# MCU.net
KiCad netlist of a schematic drawn in Altium Designer
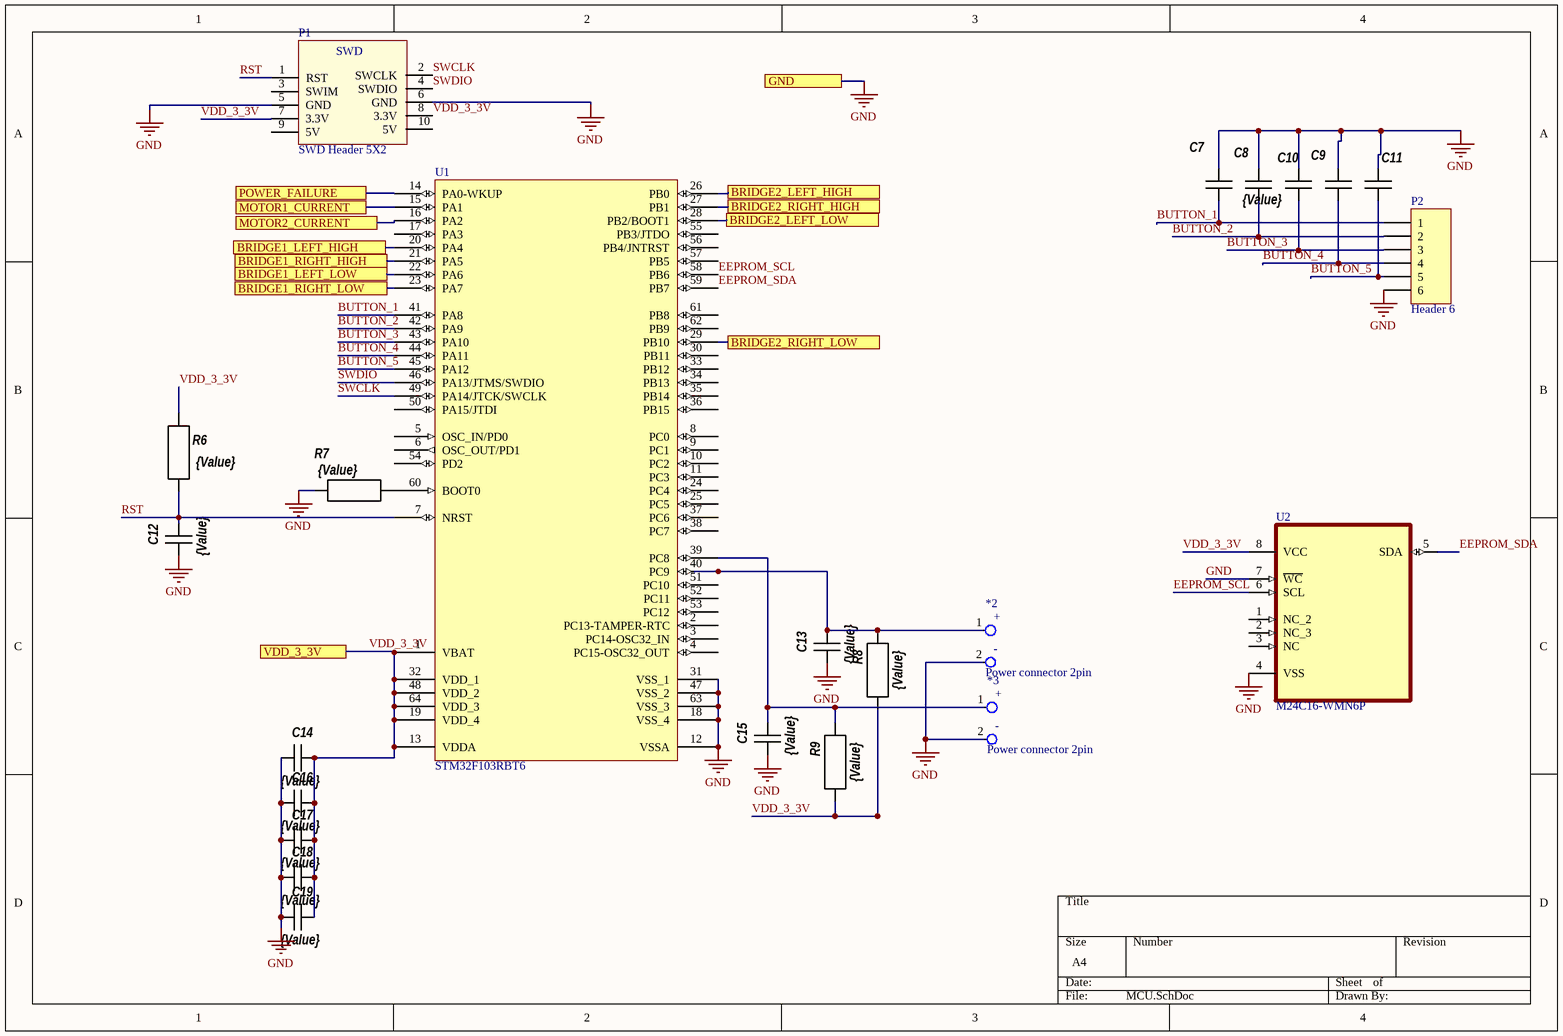
[diagram p0: MCU.SchDoc]

(export (version "E")
  (design (tool "Eeschema 10.0.6"))
  (components
    (comp (ref "*2")
      (value "Power connector 2pin")
      (footprint "Power connector 2 pin")
      (libsource (lib "Integrated_Library1") (part "Power connector 2pin"))
    )
    (comp (ref "*3")
      (value "Power connector 2pin")
      (footprint "Power connector 2 pin")
      (libsource (lib "Integrated_Library1") (part "Power connector 2pin"))
    )
    (comp (ref "C7")
      (value "{Value}")
      (footprint "R0805")
      (description "Конденсатор 0805")
      (fields (field (name "MANUFACTURER") "Murata") (field (name "Comment") "Cap 0805"))
      (libsource (lib "УГО") (part "Cap 0805"))
    )
    (comp (ref "C8")
      (value "Cap 0805")
      (footprint "R0805")
      (description "Конденсатор 0805")
      (fields (field (name "MANUFACTURER") "Murata"))
      (libsource (lib "УГО") (part "Cap 0805"))
    )
    (comp (ref "C9")
      (value "Cap 0805")
      (footprint "R0805")
      (description "Конденсатор 0805")
      (fields (field (name "MANUFACTURER") "Murata"))
      (libsource (lib "УГО") (part "Cap 0805"))
    )
    (comp (ref "C10")
      (value "Cap 0805")
      (footprint "R0805")
      (description "Конденсатор 0805")
      (fields (field (name "MANUFACTURER") "Murata"))
      (libsource (lib "УГО") (part "Cap 0805"))
    )
    (comp (ref "C11")
      (value "Cap 0805")
      (footprint "R0805")
      (description "Конденсатор 0805")
      (fields (field (name "MANUFACTURER") "Murata"))
      (libsource (lib "УГО") (part "Cap 0805"))
    )
    (comp (ref "C12")
      (value "{Value}")
      (footprint "R0805")
      (description "Конденсатор 0805")
      (fields (field (name "MANUFACTURER") "Murata") (field (name "Comment") "Cap 0805"))
      (libsource (lib "УГО") (part "Cap 0805"))
    )
    (comp (ref "C13")
      (value "{Value}")
      (footprint "R0805")
      (description "Конденсатор 0805")
      (fields (field (name "MANUFACTURER") "Murata") (field (name "Comment") "Cap 0805"))
      (libsource (lib "УГО") (part "Cap 0805"))
    )
    (comp (ref "C14")
      (value "{Value}")
      (footprint "R0805")
      (description "Конденсатор 0805")
      (fields (field (name "MANUFACTURER") "Murata") (field (name "Comment") "Cap 0805"))
      (libsource (lib "УГО") (part "Cap 0805"))
    )
    (comp (ref "C15")
      (value "{Value}")
      (footprint "R0805")
      (description "Конденсатор 0805")
      (fields (field (name "MANUFACTURER") "Murata") (field (name "Comment") "Cap 0805"))
      (libsource (lib "УГО") (part "Cap 0805"))
    )
    (comp (ref "C16")
      (value "{Value}")
      (footprint "R0805")
      (description "Конденсатор 0805")
      (fields (field (name "MANUFACTURER") "Murata") (field (name "Comment") "Cap 0805"))
      (libsource (lib "УГО") (part "Cap 0805"))
    )
    (comp (ref "C17")
      (value "{Value}")
      (footprint "R0805")
      (description "Конденсатор 0805")
      (fields (field (name "MANUFACTURER") "Murata") (field (name "Comment") "Cap 0805"))
      (libsource (lib "УГО") (part "Cap 0805"))
    )
    (comp (ref "C18")
      (value "{Value}")
      (footprint "R0805")
      (description "Конденсатор 0805")
      (fields (field (name "MANUFACTURER") "Murata") (field (name "Comment") "Cap 0805"))
      (libsource (lib "УГО") (part "Cap 0805"))
    )
    (comp (ref "C19")
      (value "{Value}")
      (footprint "R0805")
      (description "Конденсатор 0805")
      (fields (field (name "MANUFACTURER") "Murata") (field (name "Comment") "Cap 0805"))
      (libsource (lib "УГО") (part "Cap 0805"))
    )
    (comp (ref "P1")
      (value "SWD Header 5X2")
      (footprint "HDR2X5")
      (description "Header, 5-Pin, Dual row")
      (fields (field (name "PUBLISHER") "Altium Limited"))
      (libsource (lib "Integrated_Library1") (part "SWD Header 5X2"))
    )
    (comp (ref "P2")
      (value "Header 6")
      (footprint "HDR1X6")
      (description "Header, 6-Pin")
      (fields (field (name "PUBLISHER") "Altium Limited"))
      (libsource (lib "Miscellaneous Connectors") (part "Header 6"))
    )
    (comp (ref "R6")
      (value "{Value}")
      (footprint "R0805")
      (description "Резистор 0805")
      (fields (field (name "MANUFACTURER") "Yageo") (field (name "Comment") "Res 0805"))
      (libsource (lib "GIS_SMD components") (part "Res 0805"))
    )
    (comp (ref "R7")
      (value "{Value}")
      (footprint "R0805")
      (description "Резистор 0805")
      (fields (field (name "MANUFACTURER") "Yageo") (field (name "Comment") "Res 0805"))
      (libsource (lib "GIS_SMD components") (part "Res 0805"))
    )
    (comp (ref "R8")
      (value "{Value}")
      (footprint "R0805")
      (description "Резистор 0805")
      (fields (field (name "MANUFACTURER") "Yageo") (field (name "Comment") "Res 0805"))
      (libsource (lib "GIS_SMD components") (part "Res 0805"))
    )
    (comp (ref "R9")
      (value "{Value}")
      (footprint "R0805")
      (description "Резистор 0805")
      (fields (field (name "MANUFACTURER") "Yageo") (field (name "Comment") "Res 0805"))
      (libsource (lib "GIS_SMD components") (part "Res 0805"))
    )
    (comp (ref "U1")
      (value "STM32F103RBT6")
      (footprint "LQFP64_N")
      (description "STM32 ARM-based 32-bit MCU with 128 Kbytes Flash, 64-pin LQFP, Industrial Temperature")
      (fields (field (name "PUBLISHER") "Altium Limited"))
      (libsource (lib "ST Microcontroller 32-Bit STM32") (part "STM32F103RBT6"))
    )
    (comp (ref "U2")
      (value "M24C16-WMN6P")
      (footprint "SOIC127P600X175-8N")
      (description "EEPROM Memory IC 16Kb _2K x 8_ IÂ²C 400kHz 900ns 8-SO")
      (fields (field (name "MF") "STMicroelectronics"))
      (libsource (lib "M24C16-WMN6P") (part "M24C16-WMN6P"))
    )
  )
  (nets
    (net (code "1") (name "/BRIDGE1_LEFT_HIGH") (class "Default")
      (node (ref "U1") (pin "20") (pinfunction "PA4_20") (pintype "bidirectional"))
    )
    (net (code "2") (name "/BRIDGE1_LEFT_LOW") (class "Default")
      (node (ref "U1") (pin "22") (pinfunction "PA6_22") (pintype "bidirectional"))
    )
    (net (code "3") (name "/BRIDGE1_RIGHT_HIGH") (class "Default")
      (node (ref "U1") (pin "21") (pinfunction "PA5_21") (pintype "bidirectional"))
    )
    (net (code "4") (name "/BRIDGE1_RIGHT_LOW") (class "Default")
      (node (ref "U1") (pin "23") (pinfunction "PA7_23") (pintype "bidirectional"))
    )
    (net (code "5") (name "/BRIDGE2_LEFT_HIGH") (class "Default")
      (node (ref "U1") (pin "26") (pinfunction "PB0_26") (pintype "bidirectional"))
    )
    (net (code "6") (name "/BRIDGE2_LEFT_LOW") (class "Default")
      (node (ref "U1") (pin "28") (pinfunction "PB2/BOOT1_28") (pintype "bidirectional"))
    )
    (net (code "7") (name "/BRIDGE2_RIGHT_HIGH") (class "Default")
      (node (ref "U1") (pin "27") (pinfunction "PB1_27") (pintype "bidirectional"))
    )
    (net (code "8") (name "/BRIDGE2_RIGHT_LOW") (class "Default")
      (node (ref "U1") (pin "29") (pinfunction "PB10_29") (pintype "bidirectional"))
    )
    (net (code "9") (name "/BUTTON_1") (class "Default")
      (node (ref "C7") (pin "1") (pinfunction "1_1") (pintype "passive"))
      (node (ref "P2") (pin "1") (pinfunction "1_1") (pintype "passive"))
      (node (ref "U1") (pin "41") (pinfunction "PA8_41") (pintype "bidirectional"))
    )
    (net (code "10") (name "/BUTTON_2") (class "Default")
      (node (ref "C8") (pin "1") (pinfunction "1_1") (pintype "passive"))
      (node (ref "P2") (pin "2") (pinfunction "2_2") (pintype "passive"))
      (node (ref "U1") (pin "42") (pinfunction "PA9_42") (pintype "bidirectional"))
    )
    (net (code "11") (name "/BUTTON_3") (class "Default")
      (node (ref "C10") (pin "1") (pinfunction "1_1") (pintype "passive"))
      (node (ref "P2") (pin "3") (pinfunction "3_3") (pintype "passive"))
      (node (ref "U1") (pin "43") (pinfunction "PA10_43") (pintype "bidirectional"))
    )
    (net (code "12") (name "/BUTTON_4") (class "Default")
      (node (ref "C9") (pin "1") (pinfunction "1_1") (pintype "passive"))
      (node (ref "P2") (pin "4") (pinfunction "4_4") (pintype "passive"))
      (node (ref "U1") (pin "44") (pinfunction "PA11_44") (pintype "bidirectional"))
    )
    (net (code "13") (name "/BUTTON_5") (class "Default")
      (node (ref "C11") (pin "1") (pinfunction "1_1") (pintype "passive"))
      (node (ref "P2") (pin "5") (pinfunction "5_5") (pintype "passive"))
      (node (ref "U1") (pin "45") (pinfunction "PA12_45") (pintype "bidirectional"))
    )
    (net (code "14") (name "/EEPROM_SCL") (class "Default")
      (node (ref "U1") (pin "58") (pinfunction "PB6_58") (pintype "bidirectional"))
      (node (ref "U2") (pin "6") (pinfunction "SCL_6") (pintype "input"))
    )
    (net (code "15") (name "/EEPROM_SDA") (class "Default")
      (node (ref "U1") (pin "59") (pinfunction "PB7_59") (pintype "bidirectional"))
      (node (ref "U2") (pin "5") (pinfunction "SDA_5") (pintype "bidirectional"))
    )
    (net (code "16") (name "/MOTOR1_CURRENT") (class "Default")
      (node (ref "U1") (pin "15") (pinfunction "PA1_15") (pintype "bidirectional"))
    )
    (net (code "17") (name "/MOTOR2_CURRENT") (class "Default")
      (node (ref "U1") (pin "16") (pinfunction "PA2_16") (pintype "bidirectional"))
    )
    (net (code "18") (name "/POWER_FAILURE") (class "Default")
      (node (ref "U1") (pin "14") (pinfunction "PA0-WKUP_14") (pintype "bidirectional"))
    )
    (net (code "19") (name "/RST") (class "Default")
      (node (ref "C12") (pin "2") (pinfunction "2_2") (pintype "passive"))
      (node (ref "P1") (pin "1") (pinfunction "RST_1") (pintype "passive"))
      (node (ref "R6") (pin "1") (pinfunction "1_1") (pintype "passive"))
      (node (ref "U1") (pin "7") (pinfunction "NRST_7") (pintype "bidirectional"))
    )
    (net (code "20") (name "/SWCLK") (class "Default")
      (node (ref "P1") (pin "2") (pinfunction "SWCLK_2") (pintype "passive"))
      (node (ref "U1") (pin "49") (pinfunction "PA14/JTCK/SWCLK_49") (pintype "bidirectional"))
    )
    (net (code "21") (name "/SWDIO") (class "Default")
      (node (ref "P1") (pin "4") (pinfunction "SWDIO_4") (pintype "passive"))
      (node (ref "U1") (pin "46") (pinfunction "PA13/JTMS/SWDIO_46") (pintype "bidirectional"))
    )
    (net (code "22") (name "/VDD_3_3V") (class "Default")
      (node (ref "C14") (pin "2") (pinfunction "2_2") (pintype "passive"))
      (node (ref "C16") (pin "2") (pinfunction "2_2") (pintype "passive"))
      (node (ref "C17") (pin "2") (pinfunction "2_2") (pintype "passive"))
      (node (ref "C18") (pin "2") (pinfunction "2_2") (pintype "passive"))
      (node (ref "C19") (pin "2") (pinfunction "2_2") (pintype "passive"))
      (node (ref "P1") (pin "7") (pinfunction "3.3V_7") (pintype "passive"))
      (node (ref "P1") (pin "8") (pinfunction "3.3V_8") (pintype "passive"))
      (node (ref "R6") (pin "2") (pinfunction "2_2") (pintype "passive"))
      (node (ref "R8") (pin "1") (pinfunction "1_1") (pintype "passive"))
      (node (ref "R9") (pin "1") (pinfunction "1_1") (pintype "passive"))
      (node (ref "U1") (pin "1") (pinfunction "VBAT_1") (pintype "power_in"))
      (node (ref "U1") (pin "13") (pinfunction "VDDA_13") (pintype "power_in"))
      (node (ref "U1") (pin "19") (pinfunction "VDD_4_19") (pintype "power_in"))
      (node (ref "U1") (pin "32") (pinfunction "VDD_1_32") (pintype "power_in"))
      (node (ref "U1") (pin "48") (pinfunction "VDD_2_48") (pintype "power_in"))
      (node (ref "U1") (pin "64") (pinfunction "VDD_3_64") (pintype "power_in"))
      (node (ref "U2") (pin "8") (pinfunction "VCC_8") (pintype "power_in"))
    )
    (net (code "23") (name "GND") (class "Default")
      (node (ref "*2") (pin "2") (pintype "passive"))
      (node (ref "*3") (pin "2") (pintype "passive"))
      (node (ref "C10") (pin "2") (pinfunction "2_2") (pintype "passive"))
      (node (ref "C11") (pin "2") (pinfunction "2_2") (pintype "passive"))
      (node (ref "C12") (pin "1") (pinfunction "1_1") (pintype "passive"))
      (node (ref "C13") (pin "1") (pinfunction "1_1") (pintype "passive"))
      (node (ref "C14") (pin "1") (pinfunction "1_1") (pintype "passive"))
      (node (ref "C15") (pin "1") (pinfunction "1_1") (pintype "passive"))
      (node (ref "C16") (pin "1") (pinfunction "1_1") (pintype "passive"))
      (node (ref "C17") (pin "1") (pinfunction "1_1") (pintype "passive"))
      (node (ref "C18") (pin "1") (pinfunction "1_1") (pintype "passive"))
      (node (ref "C19") (pin "1") (pinfunction "1_1") (pintype "passive"))
      (node (ref "C7") (pin "2") (pinfunction "2_2") (pintype "passive"))
      (node (ref "C8") (pin "2") (pinfunction "2_2") (pintype "passive"))
      (node (ref "C9") (pin "2") (pinfunction "2_2") (pintype "passive"))
      (node (ref "P1") (pin "5") (pinfunction "GND_5") (pintype "passive"))
      (node (ref "P1") (pin "6") (pinfunction "GND_6") (pintype "passive"))
      (node (ref "P2") (pin "6") (pinfunction "6_6") (pintype "passive"))
      (node (ref "R7") (pin "1") (pinfunction "1_1") (pintype "passive"))
      (node (ref "U1") (pin "12") (pinfunction "VSSA_12") (pintype "power_in"))
      (node (ref "U1") (pin "18") (pinfunction "VSS_4_18") (pintype "power_in"))
      (node (ref "U1") (pin "31") (pinfunction "VSS_1_31") (pintype "power_in"))
      (node (ref "U1") (pin "47") (pinfunction "VSS_2_47") (pintype "power_in"))
      (node (ref "U1") (pin "63") (pinfunction "VSS_3_63") (pintype "power_in"))
      (node (ref "U2") (pin "4") (pinfunction "VSS_4") (pintype "passive"))
      (node (ref "U2") (pin "7") (pinfunction "~{WC}_7") (pintype "input"))
    )
    (net (code "24") (name "Net-(U1-BOOT0)") (class "Default")
      (node (ref "R7") (pin "2") (pinfunction "2_2") (pintype "passive"))
      (node (ref "U1") (pin "60") (pinfunction "BOOT0_60") (pintype "input"))
    )
    (net (code "25") (name "Net-(U1-PC8)") (class "Default")
      (node (ref "*3") (pin "1") (pintype "passive"))
      (node (ref "C15") (pin "2") (pinfunction "2_2") (pintype "passive"))
      (node (ref "R9") (pin "2") (pinfunction "2_2") (pintype "passive"))
      (node (ref "U1") (pin "39") (pinfunction "PC8_39") (pintype "bidirectional"))
    )
    (net (code "26") (name "Net-(U1-PC9)") (class "Default")
      (node (ref "*2") (pin "1") (pintype "passive"))
      (node (ref "C13") (pin "2") (pinfunction "2_2") (pintype "passive"))
      (node (ref "R8") (pin "2") (pinfunction "2_2") (pintype "passive"))
      (node (ref "U1") (pin "40") (pinfunction "PC9_40") (pintype "bidirectional"))
    )
    (net (code "27") (name "unconnected-(P1-5V-Pad9)") (class "Default")
      (node (ref "P1") (pin "9") (pinfunction "5V_9") (pintype "passive"))
    )
    (net (code "28") (name "unconnected-(P1-5V-Pad10)") (class "Default")
      (node (ref "P1") (pin "10") (pinfunction "5V_10") (pintype "passive"))
    )
    (net (code "29") (name "unconnected-(P1-SWIM-Pad3)") (class "Default")
      (node (ref "P1") (pin "3") (pinfunction "SWIM_3") (pintype "passive"))
    )
    (net (code "30") (name "unconnected-(U1-OSC_IN{slash}PD0-Pad5)") (class "Default")
      (node (ref "U1") (pin "5") (pinfunction "OSC_IN/PD0_5") (pintype "input"))
    )
    (net (code "31") (name "unconnected-(U1-OSC_OUT{slash}PD1-Pad6)") (class "Default")
      (node (ref "U1") (pin "6") (pinfunction "OSC_OUT/PD1_6") (pintype "output"))
    )
    (net (code "32") (name "unconnected-(U1-PA3-Pad17)") (class "Default")
      (node (ref "U1") (pin "17") (pinfunction "PA3_17") (pintype "bidirectional"))
    )
    (net (code "33") (name "unconnected-(U1-PA15{slash}JTDI-Pad50)") (class "Default")
      (node (ref "U1") (pin "50") (pinfunction "PA15/JTDI_50") (pintype "bidirectional"))
    )
    (net (code "34") (name "unconnected-(U1-PB3{slash}JTDO-Pad55)") (class "Default")
      (node (ref "U1") (pin "55") (pinfunction "PB3/JTDO_55") (pintype "bidirectional"))
    )
    (net (code "35") (name "unconnected-(U1-PB4{slash}JNTRST-Pad56)") (class "Default")
      (node (ref "U1") (pin "56") (pinfunction "PB4/JNTRST_56") (pintype "bidirectional"))
    )
    (net (code "36") (name "unconnected-(U1-PB5-Pad57)") (class "Default")
      (node (ref "U1") (pin "57") (pinfunction "PB5_57") (pintype "bidirectional"))
    )
    (net (code "37") (name "unconnected-(U1-PB8-Pad61)") (class "Default")
      (node (ref "U1") (pin "61") (pinfunction "PB8_61") (pintype "bidirectional"))
    )
    (net (code "38") (name "unconnected-(U1-PB9-Pad62)") (class "Default")
      (node (ref "U1") (pin "62") (pinfunction "PB9_62") (pintype "bidirectional"))
    )
    (net (code "39") (name "unconnected-(U1-PB11-Pad30)") (class "Default")
      (node (ref "U1") (pin "30") (pinfunction "PB11_30") (pintype "bidirectional"))
    )
    (net (code "40") (name "unconnected-(U1-PB12-Pad33)") (class "Default")
      (node (ref "U1") (pin "33") (pinfunction "PB12_33") (pintype "bidirectional"))
    )
    (net (code "41") (name "unconnected-(U1-PB13-Pad34)") (class "Default")
      (node (ref "U1") (pin "34") (pinfunction "PB13_34") (pintype "bidirectional"))
    )
    (net (code "42") (name "unconnected-(U1-PB14-Pad35)") (class "Default")
      (node (ref "U1") (pin "35") (pinfunction "PB14_35") (pintype "bidirectional"))
    )
    (net (code "43") (name "unconnected-(U1-PB15-Pad36)") (class "Default")
      (node (ref "U1") (pin "36") (pinfunction "PB15_36") (pintype "bidirectional"))
    )
    (net (code "44") (name "unconnected-(U1-PC0-Pad8)") (class "Default")
      (node (ref "U1") (pin "8") (pinfunction "PC0_8") (pintype "bidirectional"))
    )
    (net (code "45") (name "unconnected-(U1-PC1-Pad9)") (class "Default")
      (node (ref "U1") (pin "9") (pinfunction "PC1_9") (pintype "bidirectional"))
    )
    (net (code "46") (name "unconnected-(U1-PC2-Pad10)") (class "Default")
      (node (ref "U1") (pin "10") (pinfunction "PC2_10") (pintype "bidirectional"))
    )
    (net (code "47") (name "unconnected-(U1-PC3-Pad11)") (class "Default")
      (node (ref "U1") (pin "11") (pinfunction "PC3_11") (pintype "bidirectional"))
    )
    (net (code "48") (name "unconnected-(U1-PC4-Pad24)") (class "Default")
      (node (ref "U1") (pin "24") (pinfunction "PC4_24") (pintype "bidirectional"))
    )
    (net (code "49") (name "unconnected-(U1-PC5-Pad25)") (class "Default")
      (node (ref "U1") (pin "25") (pinfunction "PC5_25") (pintype "bidirectional"))
    )
    (net (code "50") (name "unconnected-(U1-PC6-Pad37)") (class "Default")
      (node (ref "U1") (pin "37") (pinfunction "PC6_37") (pintype "bidirectional"))
    )
    (net (code "51") (name "unconnected-(U1-PC7-Pad38)") (class "Default")
      (node (ref "U1") (pin "38") (pinfunction "PC7_38") (pintype "bidirectional"))
    )
    (net (code "52") (name "unconnected-(U1-PC10-Pad51)") (class "Default")
      (node (ref "U1") (pin "51") (pinfunction "PC10_51") (pintype "bidirectional"))
    )
    (net (code "53") (name "unconnected-(U1-PC11-Pad52)") (class "Default")
      (node (ref "U1") (pin "52") (pinfunction "PC11_52") (pintype "bidirectional"))
    )
    (net (code "54") (name "unconnected-(U1-PC12-Pad53)") (class "Default")
      (node (ref "U1") (pin "53") (pinfunction "PC12_53") (pintype "bidirectional"))
    )
    (net (code "55") (name "unconnected-(U1-PC13-TAMPER-RTC-Pad2)") (class "Default")
      (node (ref "U1") (pin "2") (pinfunction "PC13-TAMPER-RTC_2") (pintype "bidirectional"))
    )
    (net (code "56") (name "unconnected-(U1-PC14-OSC32_IN-Pad3)") (class "Default")
      (node (ref "U1") (pin "3") (pinfunction "PC14-OSC32_IN_3") (pintype "bidirectional"))
    )
    (net (code "57") (name "unconnected-(U1-PC15-OSC32_OUT-Pad4)") (class "Default")
      (node (ref "U1") (pin "4") (pinfunction "PC15-OSC32_OUT_4") (pintype "bidirectional"))
    )
    (net (code "58") (name "unconnected-(U1-PD2-Pad54)") (class "Default")
      (node (ref "U1") (pin "54") (pinfunction "PD2_54") (pintype "bidirectional"))
    )
    (net (code "59") (name "unconnected-(U2-NC-Pad3)") (class "Default")
      (node (ref "U2") (pin "3") (pinfunction "NC_3") (pintype "input"))
    )
    (net (code "60") (name "unconnected-(U2-NC_2-Pad1)") (class "Default")
      (node (ref "U2") (pin "1") (pinfunction "NC_2_1") (pintype "input"))
    )
    (net (code "61") (name "unconnected-(U2-NC_3-Pad2)") (class "Default")
      (node (ref "U2") (pin "2") (pinfunction "NC_3_2") (pintype "input"))
    )
  )
)
